# AMP_2_0_Power_Supply.net
KiCad netlist of a schematic drawn in EAGLE
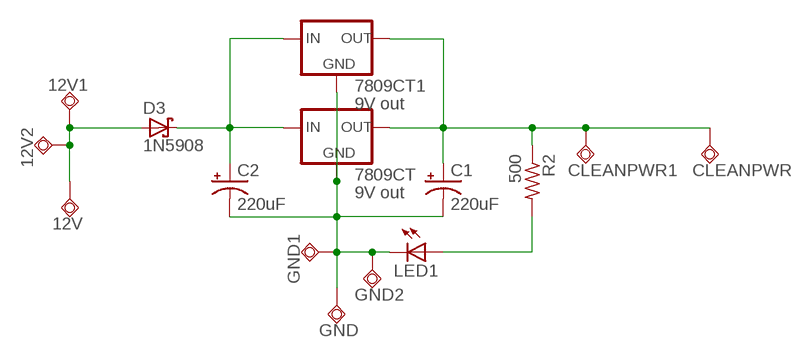
[diagram p0: schematic, sheet 1]

(export (version "E")
  (design (tool "Eeschema 10.0.6"))
  (components
    (comp (ref "12V")
      (value "TPSQPAD1-20")
      (footprint "eagle-import:P1-20")
      (libsource (lib "eagle-import") (part "TPSQPAD1-20"))
    )
    (comp (ref "12V1")
      (value "TPSQPAD1-20")
      (footprint "eagle-import:P1-20")
      (libsource (lib "eagle-import") (part "TPSQPAD1-20"))
    )
    (comp (ref "12V2")
      (value "TPSQPAD1-20")
      (footprint "eagle-import:P1-20")
      (libsource (lib "eagle-import") (part "TPSQPAD1-20"))
    )
    (comp (ref "7809CT")
      (value "9V out")
      (footprint "eagle-import:78XXS")
      (libsource (lib "eagle-import") (part "78XXS"))
    )
    (comp (ref "7809CT1")
      (value "9V out")
      (footprint "eagle-import:78XXS")
      (libsource (lib "eagle-import") (part "78XXS"))
    )
    (comp (ref "C1")
      (value "220uF")
      (footprint "eagle-import:B45181C")
      (libsource (lib "eagle-import") (part "CPOL-USB45181C"))
    )
    (comp (ref "C2")
      (value "220uF")
      (footprint "eagle-import:B45181C")
      (libsource (lib "eagle-import") (part "CPOL-USB45181C"))
    )
    (comp (ref "CLEANPWR")
      (value "TPSQPAD1-20")
      (footprint "eagle-import:P1-20")
      (libsource (lib "eagle-import") (part "TPSQPAD1-20"))
    )
    (comp (ref "CLEANPWR1")
      (value "TPSQPAD1-20")
      (footprint "eagle-import:P1-20")
      (libsource (lib "eagle-import") (part "TPSQPAD1-20"))
    )
    (comp (ref "D3")
      (value "1N5908")
      (footprint "eagle-import:C4111-15")
      (libsource (lib "eagle-import") (part "1N5908"))
    )
    (comp (ref "GND")
      (value "TPSQPAD1-20")
      (footprint "eagle-import:P1-20")
      (libsource (lib "eagle-import") (part "TPSQPAD1-20"))
    )
    (comp (ref "GND1")
      (value "TPSQPAD1-20")
      (footprint "eagle-import:P1-20")
      (libsource (lib "eagle-import") (part "TPSQPAD1-20"))
    )
    (comp (ref "GND2")
      (value "TPSQPAD1-20")
      (footprint "eagle-import:P1-20")
      (libsource (lib "eagle-import") (part "TPSQPAD1-20"))
    )
    (comp (ref "LED1")
      (value "LED5MM")
      (footprint "eagle-import:LED5MM")
      (libsource (lib "eagle-import") (part "LED5MM"))
    )
    (comp (ref "R2")
      (value "500")
      (footprint "eagle-import:0204_7")
      (libsource (lib "eagle-import") (part "R-US_0204/7"))
    )
  )
  (nets
    (net (code "1") (name "Net-(12V-PadTP)") (class "Default")
      (node (ref "12V") (pin "TP") (pinfunction "TP_TP") (pintype "input"))
      (node (ref "12V1") (pin "TP") (pinfunction "TP_TP") (pintype "input"))
      (node (ref "12V2") (pin "TP") (pinfunction "TP_TP") (pintype "input"))
      (node (ref "D3") (pin "A") (pinfunction "A_A") (pintype "passive"))
    )
    (net (code "2") (name "Net-(7809CT-PadIN)") (class "Default")
      (node (ref "7809CT") (pin "IN") (pinfunction "IN_IN") (pintype "input"))
      (node (ref "7809CT1") (pin "IN") (pinfunction "IN_IN") (pintype "input"))
      (node (ref "C2") (pin "+") (pinfunction "+_+") (pintype "passive"))
      (node (ref "D3") (pin "C") (pinfunction "C_C") (pintype "passive"))
    )
    (net (code "3") (name "Net-(7809CT-PadOUT)") (class "Default")
      (node (ref "7809CT") (pin "OUT") (pinfunction "OUT_OUT") (pintype "passive"))
      (node (ref "7809CT1") (pin "OUT") (pinfunction "OUT_OUT") (pintype "passive"))
      (node (ref "C1") (pin "+") (pinfunction "+_+") (pintype "passive"))
      (node (ref "CLEANPWR") (pin "TP") (pinfunction "TP_TP") (pintype "input"))
      (node (ref "CLEANPWR1") (pin "TP") (pinfunction "TP_TP") (pintype "input"))
      (node (ref "R2") (pin "1") (pinfunction "1_1") (pintype "passive"))
    )
    (net (code "4") (name "Net-(LED1-C)") (class "Default")
      (node (ref "7809CT") (pin "GND") (pinfunction "GND_GND") (pintype "input"))
      (node (ref "7809CT1") (pin "GND") (pinfunction "GND_GND") (pintype "input"))
      (node (ref "C1") (pin "-") (pinfunction "-_-") (pintype "passive"))
      (node (ref "C2") (pin "-") (pinfunction "-_-") (pintype "passive"))
      (node (ref "GND") (pin "TP") (pinfunction "TP_TP") (pintype "input"))
      (node (ref "GND1") (pin "TP") (pinfunction "TP_TP") (pintype "input"))
      (node (ref "GND2") (pin "TP") (pinfunction "TP_TP") (pintype "input"))
      (node (ref "LED1") (pin "K") (pinfunction "C_K") (pintype "passive"))
    )
    (net (code "5") (name "Net-(LED1-PadA)") (class "Default")
      (node (ref "LED1") (pin "A") (pinfunction "A_A") (pintype "passive"))
      (node (ref "R2") (pin "2") (pinfunction "2_2") (pintype "passive"))
    )
  )
)
